# stm32_module.net
KiCad netlist of a schematic drawn in Altium Designer
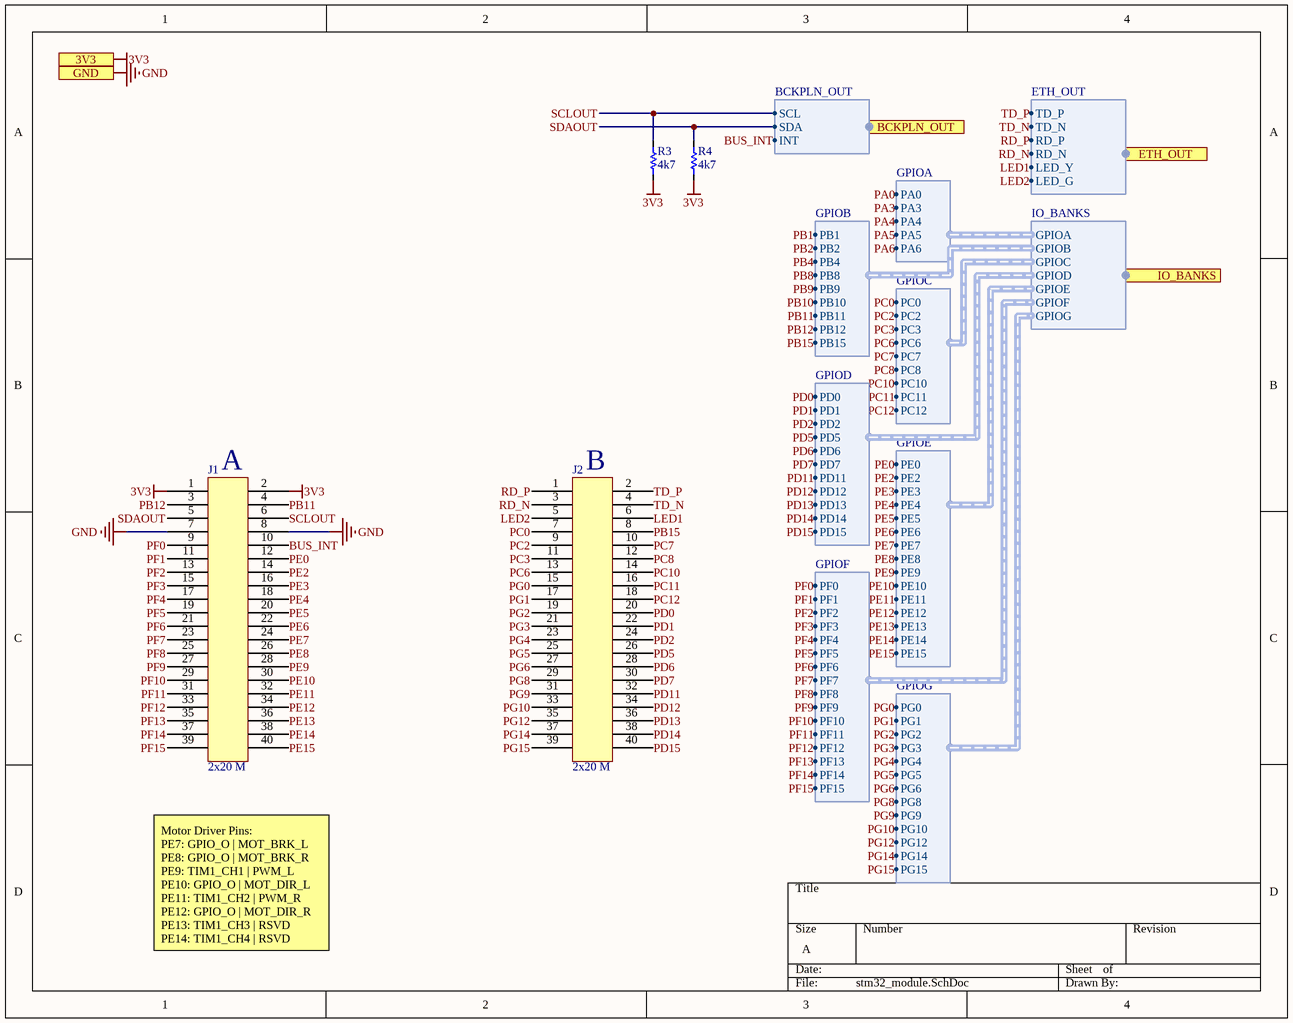
[diagram p0: stm32_module.SchDoc]

(export (version "E")
  (design (tool "Eeschema 10.0.6"))
  (components
    (comp (ref "J1")
      (value "2x20 M")
      (footprint "CONN HDR 2x20 M TOP")
      (description "CONN Header 2x20 M")
      (libsource (lib "streetbot") (part "CONN Header 2x20 M"))
    )
    (comp (ref "J2")
      (value "2x20 M")
      (footprint "CONN HDR 2x20 M TOP")
      (description "CONN Header 2x20 M")
      (libsource (lib "streetbot") (part "CONN Header 2x20 M"))
    )
    (comp (ref "R3")
      (value "4k7")
      (footprint "RES 0603 L")
      (description "RES 0603")
      (libsource (lib "streetbot") (part "RES 0603"))
    )
    (comp (ref "R4")
      (value "4k7")
      (footprint "RES 0603 L")
      (description "RES 0603")
      (libsource (lib "streetbot") (part "RES 0603"))
    )
  )
  (nets
    (net (code "9") (name "/BUS_INT") (class "Default") (node (ref "J1") (pin "10") (pintype "passive")))
    (net (code "11") (name "/LED1") (class "Default") (node (ref "J2") (pin "6") (pintype "passive")))
    (net (code "12") (name "/LED2") (class "Default") (node (ref "J2") (pin "5") (pintype "passive")))
    (net (code "24") (name "/PB11") (class "Default") (node (ref "J1") (pin "4") (pintype "passive")))
    (net (code "25") (name "/PB12") (class "Default") (node (ref "J1") (pin "3") (pintype "passive")))
    (net (code "26") (name "/PB15") (class "Default") (node (ref "J2") (pin "8") (pintype "passive")))
    (net (code "27") (name "/PC0") (class "Default") (node (ref "J2") (pin "7") (pintype "passive")))
    (net (code "28") (name "/PC2") (class "Default") (node (ref "J2") (pin "9") (pintype "passive")))
    (net (code "29") (name "/PC3") (class "Default") (node (ref "J2") (pin "11") (pintype "passive")))
    (net (code "30") (name "/PC6") (class "Default") (node (ref "J2") (pin "13") (pintype "passive")))
    (net (code "31") (name "/PC7") (class "Default") (node (ref "J2") (pin "10") (pintype "passive")))
    (net (code "32") (name "/PC8") (class "Default") (node (ref "J2") (pin "12") (pintype "passive")))
    (net (code "33") (name "/PC10") (class "Default") (node (ref "J2") (pin "14") (pintype "passive")))
    (net (code "34") (name "/PC11") (class "Default") (node (ref "J2") (pin "16") (pintype "passive")))
    (net (code "35") (name "/PC12") (class "Default") (node (ref "J2") (pin "18") (pintype "passive")))
    (net (code "36") (name "/PD0") (class "Default") (node (ref "J2") (pin "20") (pintype "passive")))
    (net (code "37") (name "/PD1") (class "Default") (node (ref "J2") (pin "22") (pintype "passive")))
    (net (code "38") (name "/PD2") (class "Default") (node (ref "J2") (pin "24") (pintype "passive")))
    (net (code "39") (name "/PD5") (class "Default") (node (ref "J2") (pin "26") (pintype "passive")))
    (net (code "40") (name "/PD6") (class "Default") (node (ref "J2") (pin "28") (pintype "passive")))
    (net (code "41") (name "/PD7") (class "Default") (node (ref "J2") (pin "30") (pintype "passive")))
    (net (code "42") (name "/PD11") (class "Default") (node (ref "J2") (pin "32") (pintype "passive")))
    (net (code "43") (name "/PD12") (class "Default") (node (ref "J2") (pin "34") (pintype "passive")))
    (net (code "44") (name "/PD13") (class "Default") (node (ref "J2") (pin "36") (pintype "passive")))
    (net (code "45") (name "/PD14") (class "Default") (node (ref "J2") (pin "38") (pintype "passive")))
    (net (code "46") (name "/PD15") (class "Default") (node (ref "J2") (pin "40") (pintype "passive")))
    (net (code "47") (name "/PE0") (class "Default") (node (ref "J1") (pin "12") (pintype "passive")))
    (net (code "48") (name "/PE2") (class "Default") (node (ref "J1") (pin "14") (pintype "passive")))
    (net (code "49") (name "/PE3") (class "Default") (node (ref "J1") (pin "16") (pintype "passive")))
    (net (code "50") (name "/PE4") (class "Default") (node (ref "J1") (pin "18") (pintype "passive")))
    (net (code "51") (name "/PE5") (class "Default") (node (ref "J1") (pin "20") (pintype "passive")))
    (net (code "52") (name "/PE6") (class "Default") (node (ref "J1") (pin "22") (pintype "passive")))
    (net (code "53") (name "/PE7") (class "Default") (node (ref "J1") (pin "24") (pintype "passive")))
    (net (code "54") (name "/PE8") (class "Default") (node (ref "J1") (pin "26") (pintype "passive")))
    (net (code "55") (name "/PE9") (class "Default") (node (ref "J1") (pin "28") (pintype "passive")))
    (net (code "56") (name "/PE10") (class "Default") (node (ref "J1") (pin "30") (pintype "passive")))
    (net (code "57") (name "/PE11") (class "Default") (node (ref "J1") (pin "32") (pintype "passive")))
    (net (code "58") (name "/PE12") (class "Default") (node (ref "J1") (pin "34") (pintype "passive")))
    (net (code "59") (name "/PE13") (class "Default") (node (ref "J1") (pin "36") (pintype "passive")))
    (net (code "60") (name "/PE14") (class "Default") (node (ref "J1") (pin "38") (pintype "passive")))
    (net (code "61") (name "/PE15") (class "Default") (node (ref "J1") (pin "40") (pintype "passive")))
    (net (code "62") (name "/PF0") (class "Default") (node (ref "J1") (pin "9") (pintype "passive")))
    (net (code "63") (name "/PF1") (class "Default") (node (ref "J1") (pin "11") (pintype "passive")))
    (net (code "64") (name "/PF2") (class "Default") (node (ref "J1") (pin "13") (pintype "passive")))
    (net (code "65") (name "/PF3") (class "Default") (node (ref "J1") (pin "15") (pintype "passive")))
    (net (code "66") (name "/PF4") (class "Default") (node (ref "J1") (pin "17") (pintype "passive")))
    (net (code "67") (name "/PF5") (class "Default") (node (ref "J1") (pin "19") (pintype "passive")))
    (net (code "68") (name "/PF6") (class "Default") (node (ref "J1") (pin "21") (pintype "passive")))
    (net (code "69") (name "/PF7") (class "Default") (node (ref "J1") (pin "23") (pintype "passive")))
    (net (code "70") (name "/PF8") (class "Default") (node (ref "J1") (pin "25") (pintype "passive")))
    (net (code "71") (name "/PF9") (class "Default") (node (ref "J1") (pin "27") (pintype "passive")))
    (net (code "72") (name "/PF10") (class "Default") (node (ref "J1") (pin "29") (pintype "passive")))
    (net (code "73") (name "/PF11") (class "Default") (node (ref "J1") (pin "31") (pintype "passive")))
    (net (code "74") (name "/PF12") (class "Default") (node (ref "J1") (pin "33") (pintype "passive")))
    (net (code "75") (name "/PF13") (class "Default") (node (ref "J1") (pin "35") (pintype "passive")))
    (net (code "76") (name "/PF14") (class "Default") (node (ref "J1") (pin "37") (pintype "passive")))
    (net (code "77") (name "/PF15") (class "Default") (node (ref "J1") (pin "39") (pintype "passive")))
    (net (code "78") (name "/PG0") (class "Default") (node (ref "J2") (pin "15") (pintype "passive")))
    (net (code "79") (name "/PG1") (class "Default") (node (ref "J2") (pin "17") (pintype "passive")))
    (net (code "80") (name "/PG2") (class "Default") (node (ref "J2") (pin "19") (pintype "passive")))
    (net (code "81") (name "/PG3") (class "Default") (node (ref "J2") (pin "21") (pintype "passive")))
    (net (code "82") (name "/PG4") (class "Default") (node (ref "J2") (pin "23") (pintype "passive")))
    (net (code "83") (name "/PG5") (class "Default") (node (ref "J2") (pin "25") (pintype "passive")))
    (net (code "84") (name "/PG6") (class "Default") (node (ref "J2") (pin "27") (pintype "passive")))
    (net (code "85") (name "/PG8") (class "Default") (node (ref "J2") (pin "29") (pintype "passive")))
    (net (code "86") (name "/PG9") (class "Default") (node (ref "J2") (pin "31") (pintype "passive")))
    (net (code "87") (name "/PG10") (class "Default") (node (ref "J2") (pin "33") (pintype "passive")))
    (net (code "88") (name "/PG12") (class "Default") (node (ref "J2") (pin "35") (pintype "passive")))
    (net (code "89") (name "/PG14") (class "Default") (node (ref "J2") (pin "37") (pintype "passive")))
    (net (code "90") (name "/PG15") (class "Default") (node (ref "J2") (pin "39") (pintype "passive")))
    (net (code "91") (name "/RD_N") (class "Default") (node (ref "J2") (pin "3") (pintype "passive")))
    (net (code "92") (name "/RD_P") (class "Default") (node (ref "J2") (pin "1") (pintype "passive")))
    (net (code "93") (name "/SCLOUT") (class "Default")
      (node (ref "J1") (pin "6") (pintype "passive"))
      (node (ref "R3") (pin "2") (pinfunction "2_2") (pintype "passive"))
    )
    (net (code "94") (name "/SDAOUT") (class "Default")
      (node (ref "J1") (pin "5") (pintype "passive"))
      (node (ref "R4") (pin "2") (pinfunction "2_2") (pintype "passive"))
    )
    (net (code "95") (name "/TD_N") (class "Default") (node (ref "J2") (pin "4") (pintype "passive")))
    (net (code "96") (name "/TD_P") (class "Default") (node (ref "J2") (pin "2") (pintype "passive")))
    (net (code "104") (name "3V3") (class "Default")
      (node (ref "J1") (pin "1") (pintype "passive"))
      (node (ref "J1") (pin "2") (pintype "passive"))
      (node (ref "R3") (pin "1") (pinfunction "1_1") (pintype "passive"))
      (node (ref "R4") (pin "1") (pinfunction "1_1") (pintype "passive"))
    )
    (net (code "105") (name "GND") (class "Default")
      (node (ref "J1") (pin "7") (pintype "passive"))
      (node (ref "J1") (pin "8") (pintype "passive"))
    )
  )
)
